# NinjaPCR-131101.net
KiCad netlist of a schematic drawn in EAGLE
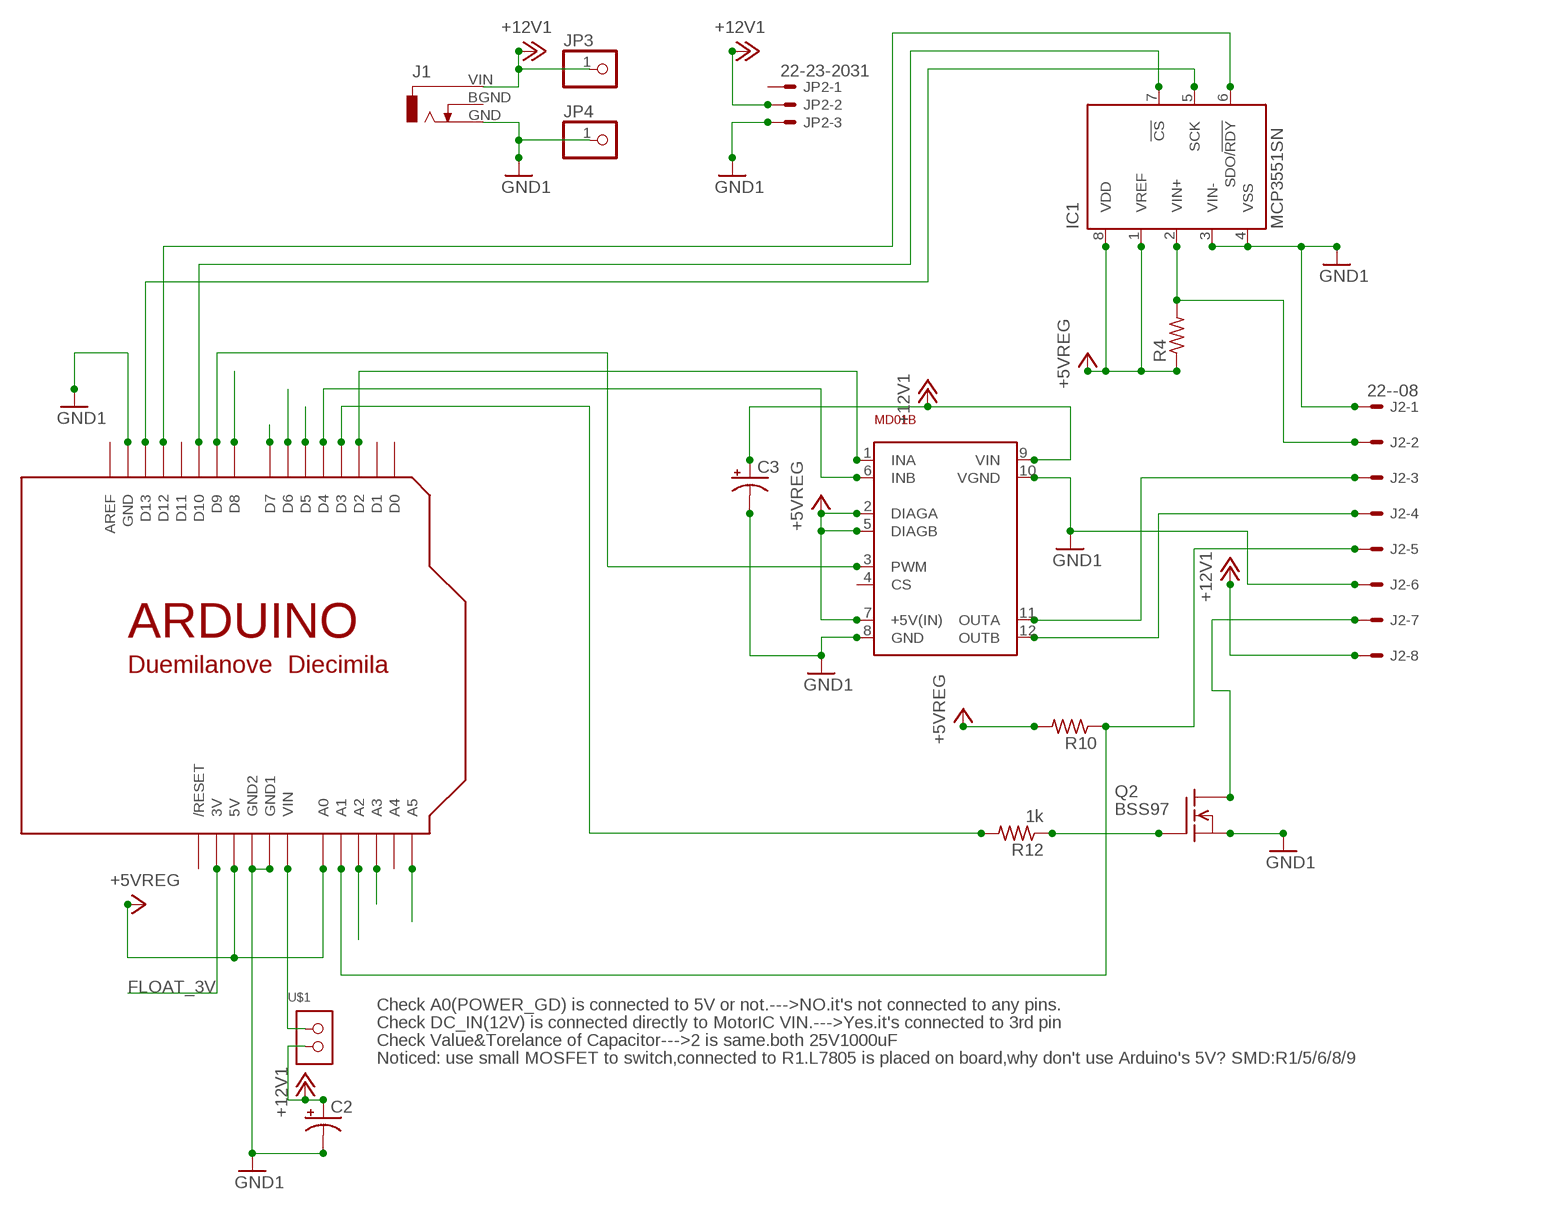
[diagram p0: schematic, sheet 1]

(export (version "E")
  (design (tool "Eeschema 10.0.6"))
  (components
    (comp (ref "C2")
      (value "CPOL-USE5-8.5")
      (footprint "eagle-import:E5-8,5")
      (libsource (lib "eagle-import") (part "CPOL-USE5-8.5"))
    )
    (comp (ref "C3")
      (value "CPOL-USE5-13")
      (footprint "eagle-import:E5-13")
      (libsource (lib "eagle-import") (part "CPOL-USE5-13"))
    )
    (comp (ref "IC1")
      (value "MCP3551SN")
      (footprint "eagle-import:SO-08")
      (fields (field (name "MPN") "MCP3551-E/SN"))
      (libsource (lib "eagle-import") (part "MCP355SN1"))
    )
    (comp (ref "J1")
      (value "DCJ0303")
      (footprint "eagle-import:DCJ0303")
      (libsource (lib "eagle-import") (part "DCJ0303"))
    )
    (comp (ref "J2")
      (value "22--08")
      (footprint "eagle-import:POLOLU-8-VERTICAL")
      (libsource (lib "eagle-import") (part "22-?-08"))
    )
    (comp (ref "JP2")
      (value "22-23-2031")
      (footprint "eagle-import:22-23-2031")
      (fields (field (name "MF") "MOLEX"))
      (libsource (lib "eagle-import") (part "22-23-2031"))
    )
    (comp (ref "JP3")
      (value "PINHD-1X1")
      (footprint "eagle-import:1X01")
      (libsource (lib "eagle-import") (part "PINHD-1X1"))
    )
    (comp (ref "JP4")
      (value "PINHD-1X1")
      (footprint "eagle-import:1X01")
      (libsource (lib "eagle-import") (part "PINHD-1X1"))
    )
    (comp (ref "MD01B")
      (value "VNH3SP30+4PINN")
      (footprint "eagle-import:VNH3SP30+4PIN_NOHOLES")
      (libsource (lib "eagle-import") (part "VNH3SP30+4PINN"))
    )
    (comp (ref "Q2")
      (value "BSS97")
      (footprint "eagle-import:TO202")
      (libsource (lib "eagle-import") (part "BSS97"))
    )
    (comp (ref "R4")
      (value "R-US_0207/10")
      (footprint "eagle-import:0207_10")
      (libsource (lib "eagle-import") (part "R-US_0207/10"))
    )
    (comp (ref "R10")
      (value "R-US_0207/10")
      (footprint "eagle-import:0207_10")
      (libsource (lib "eagle-import") (part "R-US_0207/10"))
    )
    (comp (ref "R12")
      (value "1k")
      (footprint "eagle-import:0207_10")
      (libsource (lib "eagle-import") (part "R-US_0207/10"))
    )
    (comp (ref "U$1")
      (value "1X02")
      (footprint "eagle-import:1X02_1.1_UNSIGNED")
      (libsource (lib "eagle-import") (part "1X02"))
    )
    (comp (ref "U$3")
      (value "ARDUINODUEMILANOVE")
      (footprint "eagle-import:ARDUINO")
      (libsource (lib "eagle-import") (part "ARDUINODUEMILANOVE"))
    )
  )
  (nets
    (net (code "1") (name "+5VREG") (class "Default")
      (node (ref "IC1") (pin "1") (pinfunction "VREF_1") (pintype "input"))
      (node (ref "IC1") (pin "8") (pinfunction "VDD_8") (pintype "power_in"))
      (node (ref "MD01B") (pin "2") (pinfunction "DIAGA_2") (pintype "passive"))
      (node (ref "MD01B") (pin "5") (pinfunction "DIAGB_5") (pintype "passive"))
      (node (ref "MD01B") (pin "7") (pinfunction "+5V(IN)_7") (pintype "power_in"))
      (node (ref "R10") (pin "2") (pinfunction "2_2") (pintype "passive"))
      (node (ref "R4") (pin "1") (pinfunction "1_1") (pintype "passive"))
      (node (ref "U$3") (pin "5V") (pinfunction "5V_5V") (pintype "power_in"))
      (node (ref "U$3") (pin "A0") (pinfunction "A0_A0") (pintype "bidirectional"))
    )
    (net (code "2") (name "+12V1") (class "Default")
      (node (ref "C2") (pin "+") (pinfunction "+_+") (pintype "passive"))
      (node (ref "C3") (pin "+") (pinfunction "+_+") (pintype "passive"))
      (node (ref "J1") (pin "VIN") (pinfunction "VIN_VIN") (pintype "passive"))
      (node (ref "J2") (pin "8") (pinfunction "S_8") (pintype "passive"))
      (node (ref "JP2") (pin "2") (pinfunction "S_2") (pintype "passive"))
      (node (ref "JP3") (pin "1") (pinfunction "1_1") (pintype "passive"))
      (node (ref "MD01B") (pin "9") (pinfunction "VIN_9") (pintype "power_in"))
      (node (ref "U$1") (pin "2") (pinfunction "2_2") (pintype "passive"))
    )
    (net (code "3") (name "/FLOAT_3V") (class "Default")
      (node (ref "U$3") (pin "3V") (pinfunction "3V_3V") (pintype "power_in"))
    )
    (net (code "4") (name "GND1") (class "Default")
      (node (ref "C2") (pin "-") (pinfunction "-_-") (pintype "passive"))
      (node (ref "C3") (pin "-") (pinfunction "-_-") (pintype "passive"))
      (node (ref "IC1") (pin "3") (pinfunction "VIN-_3") (pintype "input"))
      (node (ref "IC1") (pin "4") (pinfunction "VSS_4") (pintype "power_in"))
      (node (ref "J1") (pin "GND") (pinfunction "GND_GND") (pintype "passive"))
      (node (ref "J2") (pin "1") (pinfunction "S_1") (pintype "passive"))
      (node (ref "J2") (pin "6") (pinfunction "S_6") (pintype "passive"))
      (node (ref "JP2") (pin "3") (pinfunction "S_3") (pintype "passive"))
      (node (ref "JP4") (pin "1") (pinfunction "1_1") (pintype "passive"))
      (node (ref "MD01B") (pin "10") (pinfunction "VGND_10") (pintype "power_in"))
      (node (ref "MD01B") (pin "8") (pinfunction "GND_8") (pintype "power_in"))
      (node (ref "Q2") (pin "1") (pinfunction "S_1") (pintype "passive"))
      (node (ref "U$3") (pin "GND") (pinfunction "GND_GND") (pintype "power_in"))
      (node (ref "U$3") (pin "GND1") (pinfunction "GND1_GND1") (pintype "power_in"))
      (node (ref "U$3") (pin "GND2") (pinfunction "GND2_GND2") (pintype "power_in"))
    )
    (net (code "5") (name "Net-(IC1-SCK)") (class "Default")
      (node (ref "IC1") (pin "5") (pinfunction "SCK_5") (pintype "input"))
      (node (ref "U$3") (pin "D13") (pinfunction "D13_D13") (pintype "bidirectional"))
    )
    (net (code "6") (name "Net-(IC1-SDO{slash}~{RDY})") (class "Default")
      (node (ref "IC1") (pin "6") (pinfunction "SDO/~{RDY}_6") (pintype "output"))
      (node (ref "U$3") (pin "D12") (pinfunction "D12_D12") (pintype "bidirectional"))
    )
    (net (code "7") (name "Net-(IC1-VIN+)") (class "Default")
      (node (ref "IC1") (pin "2") (pinfunction "VIN+_2") (pintype "input"))
      (node (ref "J2") (pin "2") (pinfunction "S_2") (pintype "passive"))
      (node (ref "R4") (pin "2") (pinfunction "2_2") (pintype "passive"))
    )
    (net (code "8") (name "Net-(IC1-~{CS})") (class "Default")
      (node (ref "IC1") (pin "7") (pinfunction "~{CS}_7") (pintype "input"))
      (node (ref "U$3") (pin "D10") (pinfunction "D10_D10") (pintype "bidirectional"))
    )
    (net (code "9") (name "Net-(J2C-S)") (class "Default")
      (node (ref "J2") (pin "3") (pinfunction "S_3") (pintype "passive"))
      (node (ref "MD01B") (pin "11") (pinfunction "OUTA_11") (pintype "passive"))
    )
    (net (code "10") (name "Net-(J2D-S)") (class "Default")
      (node (ref "J2") (pin "4") (pinfunction "S_4") (pintype "passive"))
      (node (ref "MD01B") (pin "12") (pinfunction "OUTB_12") (pintype "passive"))
    )
    (net (code "11") (name "Net-(J2E-S)") (class "Default")
      (node (ref "J2") (pin "5") (pinfunction "S_5") (pintype "passive"))
      (node (ref "R10") (pin "1") (pinfunction "1_1") (pintype "passive"))
      (node (ref "U$3") (pin "A1") (pinfunction "A1_A1") (pintype "bidirectional"))
    )
    (net (code "12") (name "Net-(J2G-S)") (class "Default")
      (node (ref "J2") (pin "7") (pinfunction "S_7") (pintype "passive"))
      (node (ref "Q2") (pin "2") (pinfunction "D_2") (pintype "passive"))
    )
    (net (code "13") (name "Net-(MD01B-INA)") (class "Default")
      (node (ref "MD01B") (pin "1") (pinfunction "INA_1") (pintype "passive"))
      (node (ref "U$3") (pin "D2") (pinfunction "D2_D2") (pintype "bidirectional"))
    )
    (net (code "14") (name "Net-(MD01B-INB)") (class "Default")
      (node (ref "MD01B") (pin "6") (pinfunction "INB_6") (pintype "passive"))
      (node (ref "U$3") (pin "D4") (pinfunction "D4_D4") (pintype "bidirectional"))
    )
    (net (code "15") (name "Net-(MD01B-PWM)") (class "Default")
      (node (ref "MD01B") (pin "3") (pinfunction "PWM_3") (pintype "passive"))
      (node (ref "U$3") (pin "D9") (pinfunction "D9_D9") (pintype "bidirectional"))
    )
    (net (code "16") (name "Net-(Q2-G)") (class "Default")
      (node (ref "Q2") (pin "3") (pinfunction "G_3") (pintype "passive"))
      (node (ref "R12") (pin "1") (pinfunction "1_1") (pintype "passive"))
    )
    (net (code "17") (name "Net-(R12-Pad2)") (class "Default")
      (node (ref "R12") (pin "2") (pinfunction "2_2") (pintype "passive"))
      (node (ref "U$3") (pin "D3") (pinfunction "D3_D3") (pintype "bidirectional"))
    )
    (net (code "18") (name "Net-(U$1-Pad1)") (class "Default")
      (node (ref "U$1") (pin "1") (pinfunction "1_1") (pintype "passive"))
      (node (ref "U$3") (pin "VIN") (pinfunction "VIN_VIN") (pintype "power_in"))
    )
    (net (code "19") (name "unconnected-(J1-PadBGND)") (class "Default")
      (node (ref "J1") (pin "BGND") (pinfunction "BGND_BGND") (pintype "passive"))
    )
    (net (code "20") (name "unconnected-(JP2A-S-Pad1)") (class "Default")
      (node (ref "JP2") (pin "1") (pinfunction "S_1") (pintype "passive"))
    )
    (net (code "21") (name "unconnected-(MD01B-CS-Pad4)") (class "Default")
      (node (ref "MD01B") (pin "4") (pinfunction "CS_4") (pintype "passive"))
    )
    (net (code "22") (name "unconnected-(U$3-PadA2)") (class "Default")
      (node (ref "U$3") (pin "A2") (pinfunction "A2_A2") (pintype "bidirectional"))
    )
    (net (code "23") (name "unconnected-(U$3-PadA3)") (class "Default")
      (node (ref "U$3") (pin "A3") (pinfunction "A3_A3") (pintype "bidirectional"))
    )
    (net (code "24") (name "unconnected-(U$3-PadA4)") (class "Default")
      (node (ref "U$3") (pin "A4") (pinfunction "A4_A4") (pintype "bidirectional"))
    )
    (net (code "25") (name "unconnected-(U$3-PadA5)") (class "Default")
      (node (ref "U$3") (pin "A5") (pinfunction "A5_A5") (pintype "bidirectional"))
    )
    (net (code "26") (name "unconnected-(U$3-PadAREF)") (class "Default")
      (node (ref "U$3") (pin "AREF") (pinfunction "AREF_AREF") (pintype "bidirectional"))
    )
    (net (code "27") (name "unconnected-(U$3-PadD0)") (class "Default")
      (node (ref "U$3") (pin "D0") (pinfunction "D0_D0") (pintype "bidirectional"))
    )
    (net (code "28") (name "unconnected-(U$3-PadD1)") (class "Default")
      (node (ref "U$3") (pin "D1") (pinfunction "D1_D1") (pintype "bidirectional"))
    )
    (net (code "29") (name "unconnected-(U$3-PadD5)") (class "Default")
      (node (ref "U$3") (pin "D5") (pinfunction "D5_D5") (pintype "bidirectional"))
    )
    (net (code "30") (name "unconnected-(U$3-PadD6)") (class "Default")
      (node (ref "U$3") (pin "D6") (pinfunction "D6_D6") (pintype "bidirectional"))
    )
    (net (code "31") (name "unconnected-(U$3-PadD7)") (class "Default")
      (node (ref "U$3") (pin "D7") (pinfunction "D7_D7") (pintype "bidirectional"))
    )
    (net (code "32") (name "unconnected-(U$3-PadD8)") (class "Default")
      (node (ref "U$3") (pin "D8") (pinfunction "D8_D8") (pintype "bidirectional"))
    )
    (net (code "33") (name "unconnected-(U$3-PadD11)") (class "Default")
      (node (ref "U$3") (pin "D11") (pinfunction "D11_D11") (pintype "bidirectional"))
    )
    (net (code "34") (name "unconnected-(U$3-{slash}RESET-PadRESET)") (class "Default")
      (node (ref "U$3") (pin "RESET") (pinfunction "/RESET_RESET") (pintype "bidirectional"))
    )
  )
)
